# uThermometer.net
KiCad netlist of a schematic drawn in Altium Designer
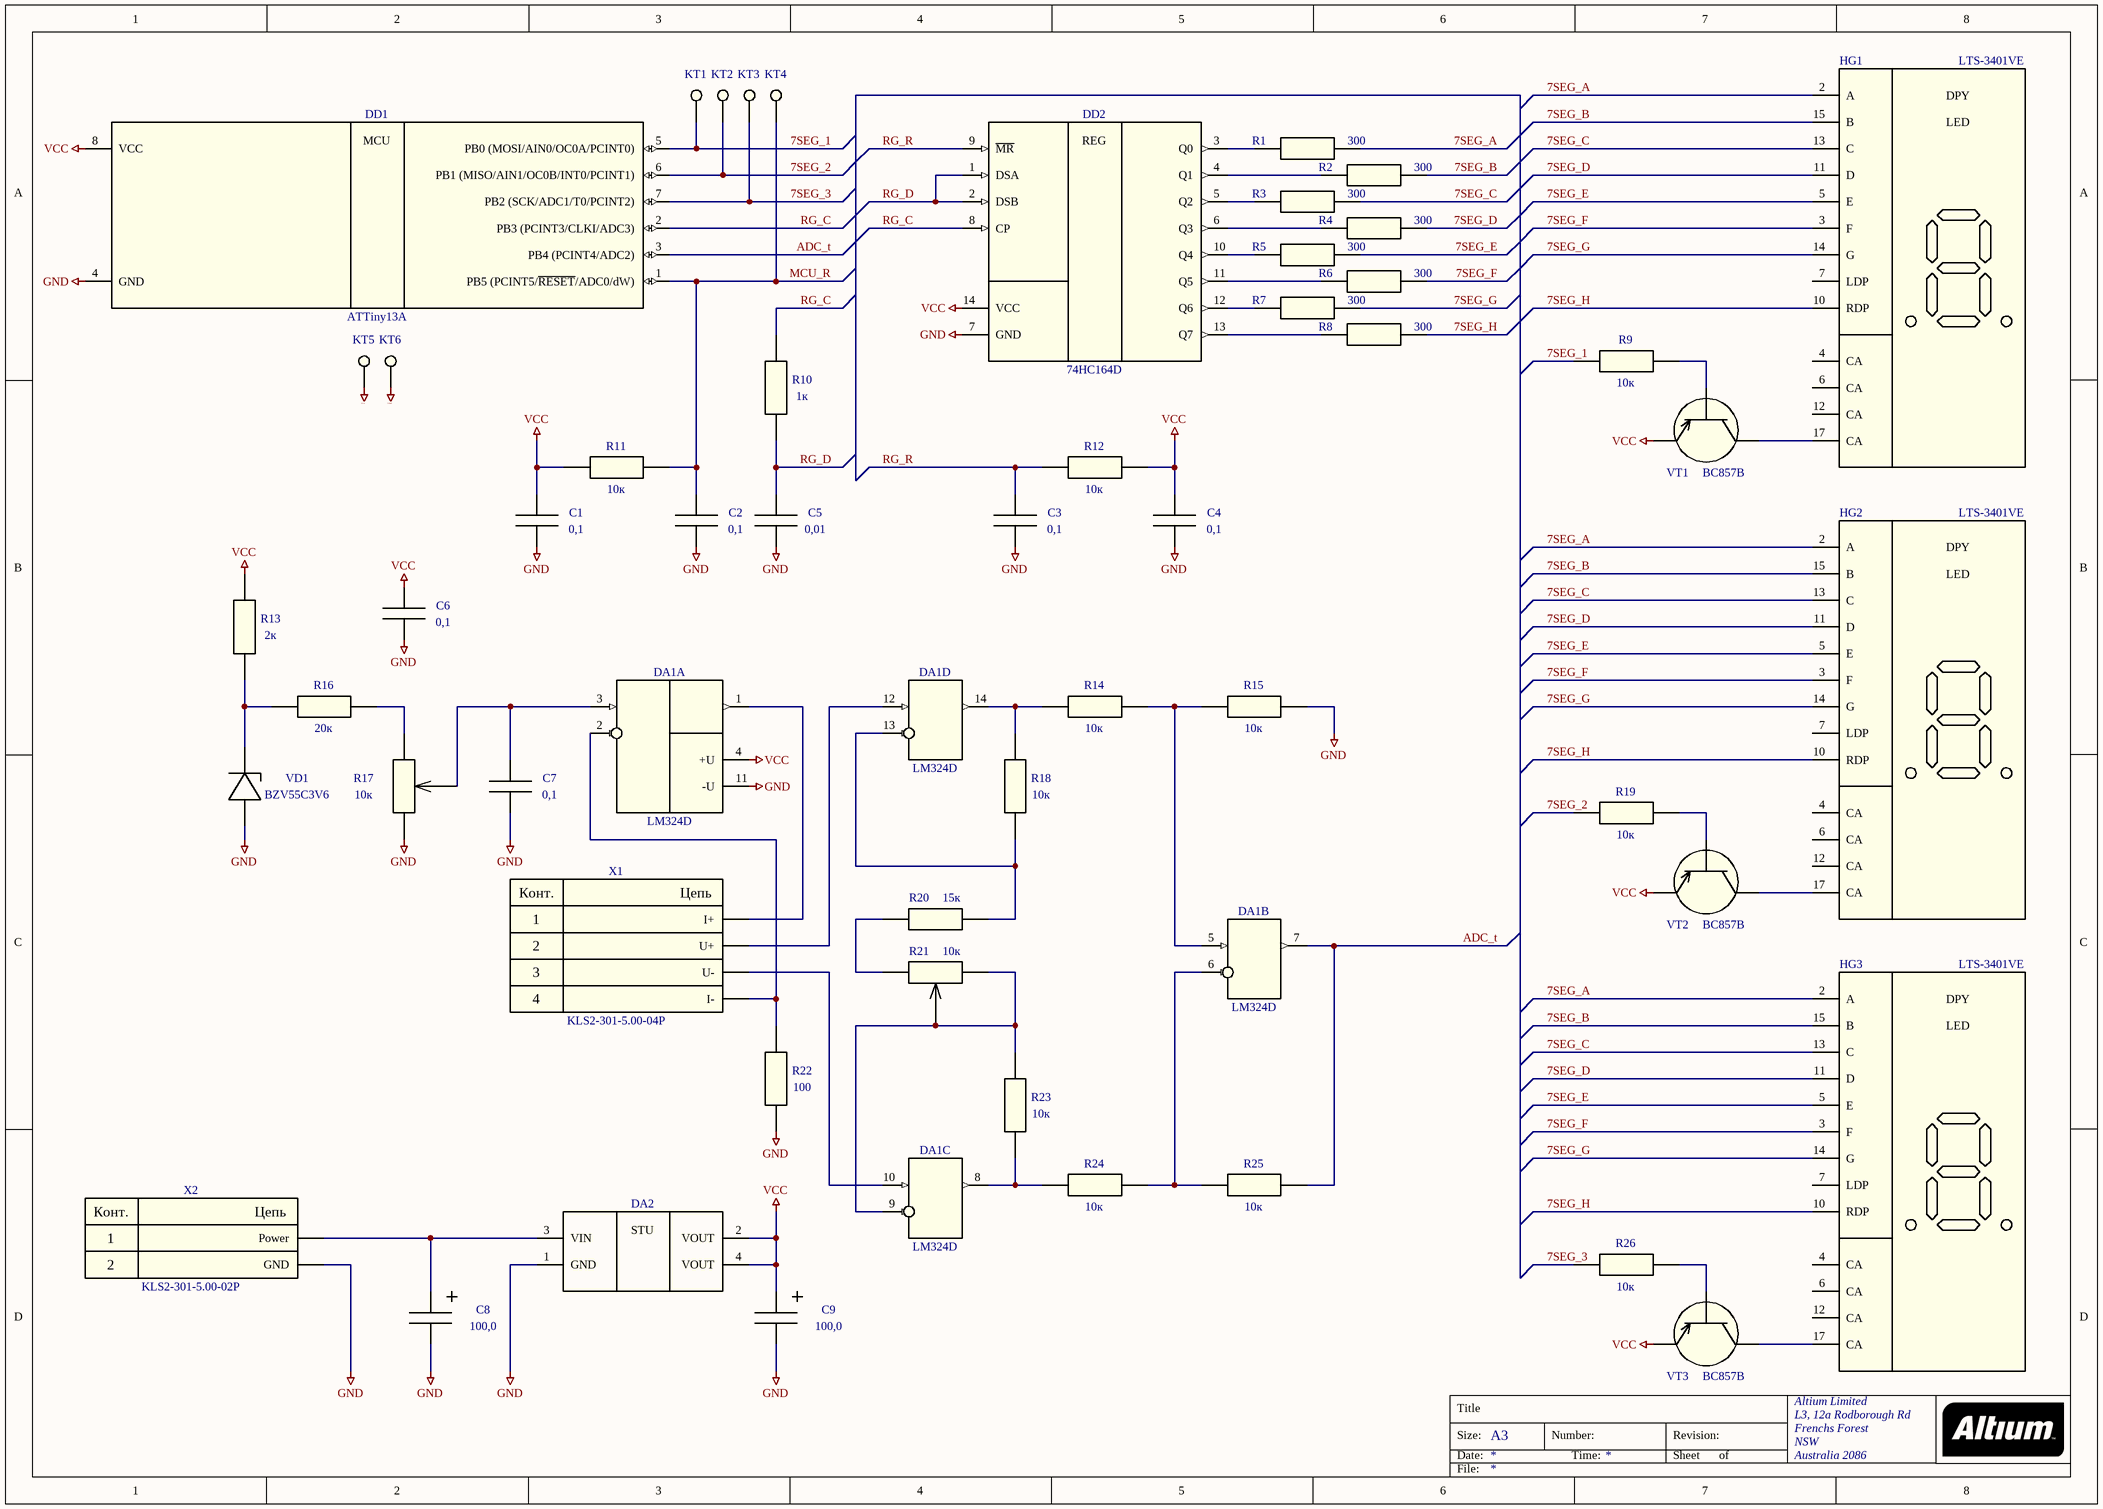
[diagram p0: uThermometer.SchDoc]

(export (version "E")
  (design (tool "Eeschema 10.0.6"))
  (components
    (comp (ref "C1")
      (value "0,1")
      (footprint "Capacitor SMD0805")
      (libsource (lib "IVV_Passive") (part "Capacitor C0805_100n"))
    )
    (comp (ref "C2")
      (value "0,1")
      (footprint "Capacitor SMD0805")
      (libsource (lib "IVV_Passive") (part "Capacitor C0805_100n"))
    )
    (comp (ref "C3")
      (value "0,1")
      (footprint "Capacitor SMD0805")
      (libsource (lib "IVV_Passive") (part "Capacitor C0805_100n"))
    )
    (comp (ref "C4")
      (value "0,1")
      (footprint "Capacitor SMD0805")
      (libsource (lib "IVV_Passive") (part "Capacitor C0805_100n"))
    )
    (comp (ref "C5")
      (value "0,01")
      (footprint "Capacitor SMD0805")
      (libsource (lib "IVV_Passive") (part "Capacitor C0805_10n"))
    )
    (comp (ref "C6")
      (value "0,1")
      (footprint "Capacitor SMD0805")
      (libsource (lib "IVV_Passive") (part "Capacitor C0805_100n"))
    )
    (comp (ref "C7")
      (value "0,1")
      (footprint "Capacitor SMD0805")
      (libsource (lib "IVV_Passive") (part "Capacitor C0805_100n"))
    )
    (comp (ref "C8")
      (value "100,0")
      (footprint "Capacitor R5V")
      (libsource (lib "IVV_Passive") (part "Capacitor R5V"))
    )
    (comp (ref "C9")
      (value "100,0")
      (footprint "Capacitor R5V")
      (libsource (lib "IVV_Passive") (part "Capacitor R5V"))
    )
    (comp (ref "DA1") (value "LM324D") (footprint "IC LM324D") (libsource (lib "IVV_IC") (part "IC LM324D")))
    (comp (ref "DA2")
      (value "LM1117I-5.0")
      (footprint "IC LM1117I-5.0")
      (libsource (lib "IVV_IC") (part "IC LM1117I-5.0"))
    )
    (comp (ref "DD1")
      (value "ATTiny13A")
      (footprint "IC ATTiny13A")
      (libsource (lib "IVV_IC") (part "IC ATTiny13A"))
    )
    (comp (ref "DD2")
      (value "74HC164D")
      (footprint "IC 74HC164D")
      (libsource (lib "IVV_IC") (part "IC 74HC164D"))
    )
    (comp (ref "HG1")
      (value "LTS-3401VE")
      (footprint "Indicator LTS3401VE")
      (libsource (lib "IVV_Lib") (part "Indicator LTS-3401VE"))
    )
    (comp (ref "HG2")
      (value "LTS-3401VE")
      (footprint "Indicator LTS3401VE")
      (libsource (lib "IVV_Lib") (part "Indicator LTS-3401VE"))
    )
    (comp (ref "HG3")
      (value "LTS-3401VE")
      (footprint "Indicator LTS3401VE")
      (libsource (lib "IVV_Lib") (part "Indicator LTS-3401VE"))
    )
    (comp (ref "KT1")
      (value "TestPoint 1")
      (footprint "TestPoint 1")
      (libsource (lib "IVV_Lib") (part "TestPoint 1"))
    )
    (comp (ref "KT2")
      (value "TestPoint 1")
      (footprint "TestPoint 1")
      (libsource (lib "IVV_Lib") (part "TestPoint 1"))
    )
    (comp (ref "KT3")
      (value "TestPoint 1")
      (footprint "TestPoint 1")
      (libsource (lib "IVV_Lib") (part "TestPoint 1"))
    )
    (comp (ref "KT4")
      (value "TestPoint 1")
      (footprint "TestPoint 1")
      (libsource (lib "IVV_Lib") (part "TestPoint 1"))
    )
    (comp (ref "KT5")
      (value "TestPoint 1")
      (footprint "TestPoint 1")
      (libsource (lib "IVV_Lib") (part "TestPoint 1"))
    )
    (comp (ref "KT6")
      (value "TestPoint 1")
      (footprint "TestPoint 1")
      (libsource (lib "IVV_Lib") (part "TestPoint 1"))
    )
    (comp (ref "R1")
      (value "300")
      (footprint "Resistor SMD0805")
      (libsource (lib "IVV_Passive") (part "Resistor R0805_300_5%"))
    )
    (comp (ref "R2")
      (value "300")
      (footprint "Resistor SMD0805")
      (libsource (lib "IVV_Passive") (part "Resistor R0805_300_5%"))
    )
    (comp (ref "R3")
      (value "300")
      (footprint "Resistor SMD0805")
      (libsource (lib "IVV_Passive") (part "Resistor R0805_300_5%"))
    )
    (comp (ref "R4")
      (value "300")
      (footprint "Resistor SMD0805")
      (libsource (lib "IVV_Passive") (part "Resistor R0805_300_5%"))
    )
    (comp (ref "R5")
      (value "300")
      (footprint "Resistor SMD0805")
      (libsource (lib "IVV_Passive") (part "Resistor R0805_300_5%"))
    )
    (comp (ref "R6")
      (value "300")
      (footprint "Resistor SMD0805")
      (libsource (lib "IVV_Passive") (part "Resistor R0805_300_5%"))
    )
    (comp (ref "R7")
      (value "300")
      (footprint "Resistor SMD0805")
      (libsource (lib "IVV_Passive") (part "Resistor R0805_300_5%"))
    )
    (comp (ref "R8")
      (value "300")
      (footprint "Resistor SMD0805")
      (libsource (lib "IVV_Passive") (part "Resistor R0805_300_5%"))
    )
    (comp (ref "R9")
      (value "10к")
      (footprint "Resistor SMD0805")
      (libsource (lib "IVV_Passive") (part "Resistor R0805_10k_5%"))
    )
    (comp (ref "R10")
      (value "1к")
      (footprint "Resistor SMD0805")
      (libsource (lib "IVV_Passive") (part "Resistor R0805_1k_5%"))
    )
    (comp (ref "R11")
      (value "10к")
      (footprint "Resistor SMD0805")
      (libsource (lib "IVV_Passive") (part "Resistor R0805_10k_5%"))
    )
    (comp (ref "R12")
      (value "10к")
      (footprint "Resistor SMD0805")
      (libsource (lib "") (part "Resistor R0805_10k_5%_1"))
    )
    (comp (ref "R13")
      (value "2к")
      (footprint "Resistor SMD0805")
      (libsource (lib "IVV_Passive") (part "Resistor R0805_2k_5%"))
    )
    (comp (ref "R14")
      (value "10к")
      (footprint "Resistor SMD0805")
      (libsource (lib "IVV_Passive") (part "Resistor R0805_10k_5%"))
    )
    (comp (ref "R15")
      (value "10к")
      (footprint "Resistor SMD0805")
      (libsource (lib "IVV_Passive") (part "Resistor R0805_10k_5%"))
    )
    (comp (ref "R16")
      (value "20к")
      (footprint "Resistor SMD0805")
      (libsource (lib "IVV_Passive") (part "Resistor R0805_20k_5%"))
    )
    (comp (ref "R17")
      (value "10к")
      (footprint "Resistor 3296W")
      (libsource (lib "") (part "Resistor 3296W _10k_1%_1"))
    )
    (comp (ref "R18")
      (value "10к")
      (footprint "Resistor SMD0805")
      (libsource (lib "") (part "Resistor R0805_10k_5%_2"))
    )
    (comp (ref "R19")
      (value "10к")
      (footprint "Resistor SMD0805")
      (libsource (lib "IVV_Passive") (part "Resistor R0805_10k_5%"))
    )
    (comp (ref "R20")
      (value "15к")
      (footprint "Resistor SMD0805")
      (libsource (lib "IVV_Passive") (part "Resistor R0805_15k_5%"))
    )
    (comp (ref "R21")
      (value "10к")
      (footprint "Resistor 3296W")
      (libsource (lib "IVV_Passive") (part "Resistor 3296W _10k_1%"))
    )
    (comp (ref "R22")
      (value "100")
      (footprint "Resistor SMD0805")
      (libsource (lib "IVV_Passive") (part "Resistor R0805_100_5%"))
    )
    (comp (ref "R23")
      (value "10к")
      (footprint "Resistor SMD0805")
      (libsource (lib "") (part "Resistor R0805_10k_5%_2"))
    )
    (comp (ref "R24")
      (value "10к")
      (footprint "Resistor SMD0805")
      (libsource (lib "IVV_Passive") (part "Resistor R0805_10k_5%"))
    )
    (comp (ref "R25")
      (value "10к")
      (footprint "Resistor SMD0805")
      (libsource (lib "IVV_Passive") (part "Resistor R0805_10k_5%"))
    )
    (comp (ref "R26")
      (value "10к")
      (footprint "Resistor SMD0805")
      (libsource (lib "IVV_Passive") (part "Resistor R0805_10k_5%"))
    )
    (comp (ref "VD1")
      (value "BZV55C3V6")
      (footprint "Zener BZV55C")
      (libsource (lib "IVV_Lib") (part "Zener BZV55C3V6"))
    )
    (comp (ref "VT1")
      (value "BC857B")
      (footprint "Transistor SOT23")
      (libsource (lib "IVV_Lib") (part "Transistor BC857B"))
    )
    (comp (ref "VT2")
      (value "BC857B")
      (footprint "Transistor SOT23")
      (libsource (lib "IVV_Lib") (part "Transistor BC857B"))
    )
    (comp (ref "VT3")
      (value "BC857B")
      (footprint "Transistor SOT23")
      (libsource (lib "IVV_Lib") (part "Transistor BC857B"))
    )
    (comp (ref "X1")
      (value "KLS2-301-5.00-04P")
      (footprint "Terminal KLS2-301-5.00-04P")
      (libsource (lib "IVV_Connectors") (part "Terminal KLS2-301-5.00-04P"))
    )
    (comp (ref "X2")
      (value "KLS2-301-5.00-02P")
      (footprint "Terminal KLS2-301-5.00-02P")
      (libsource (lib "IVV_Connectors") (part "Terminal KLS2-301-5.00-02P"))
    )
  )
  (nets
    (net (code "1") (name "/7SEG_1") (class "Default")
      (node (ref "DD1") (pin "5") (pinfunction "PB0_(MOSI/AIN0/OC0A/PCINT0)_5") (pintype "bidirectional"))
      (node (ref "KT1") (pin "1") (pinfunction "1_1") (pintype "passive"))
      (node (ref "R9") (pin "1") (pinfunction "1_1") (pintype "passive"))
    )
    (net (code "2") (name "/7SEG_2") (class "Default")
      (node (ref "DD1") (pin "6") (pinfunction "PB1_(MISO/AIN1/OC0B/INT0/PCINT1)_6") (pintype "bidirectional"))
      (node (ref "KT2") (pin "1") (pinfunction "1_1") (pintype "passive"))
      (node (ref "R19") (pin "1") (pinfunction "1_1") (pintype "passive"))
    )
    (net (code "3") (name "/7SEG_3") (class "Default")
      (node (ref "DD1") (pin "7") (pinfunction "PB2_(SCK/ADC1/T0/PCINT2)_7") (pintype "bidirectional"))
      (node (ref "KT3") (pin "1") (pinfunction "1_1") (pintype "passive"))
      (node (ref "R26") (pin "1") (pinfunction "1_1") (pintype "passive"))
    )
    (net (code "4") (name "/7SEG_A") (class "Default")
      (node (ref "HG1") (pin "2") (pinfunction "A_2") (pintype "passive"))
      (node (ref "HG2") (pin "2") (pinfunction "A_2") (pintype "passive"))
      (node (ref "HG3") (pin "2") (pinfunction "A_2") (pintype "passive"))
      (node (ref "R1") (pin "1") (pinfunction "1_1") (pintype "passive"))
    )
    (net (code "5") (name "/7SEG_B") (class "Default")
      (node (ref "HG1") (pin "15") (pinfunction "B_15") (pintype "passive"))
      (node (ref "HG2") (pin "15") (pinfunction "B_15") (pintype "passive"))
      (node (ref "HG3") (pin "15") (pinfunction "B_15") (pintype "passive"))
      (node (ref "R2") (pin "1") (pinfunction "1_1") (pintype "passive"))
    )
    (net (code "6") (name "/7SEG_C") (class "Default")
      (node (ref "HG1") (pin "13") (pinfunction "C_13") (pintype "passive"))
      (node (ref "HG2") (pin "13") (pinfunction "C_13") (pintype "passive"))
      (node (ref "HG3") (pin "13") (pinfunction "C_13") (pintype "passive"))
      (node (ref "R3") (pin "1") (pinfunction "1_1") (pintype "passive"))
    )
    (net (code "7") (name "/7SEG_D") (class "Default")
      (node (ref "HG1") (pin "11") (pinfunction "D_11") (pintype "passive"))
      (node (ref "HG2") (pin "11") (pinfunction "D_11") (pintype "passive"))
      (node (ref "HG3") (pin "11") (pinfunction "D_11") (pintype "passive"))
      (node (ref "R4") (pin "1") (pinfunction "1_1") (pintype "passive"))
    )
    (net (code "8") (name "/7SEG_E") (class "Default")
      (node (ref "HG1") (pin "5") (pinfunction "E_5") (pintype "passive"))
      (node (ref "HG2") (pin "5") (pinfunction "E_5") (pintype "passive"))
      (node (ref "HG3") (pin "5") (pinfunction "E_5") (pintype "passive"))
      (node (ref "R5") (pin "1") (pinfunction "1_1") (pintype "passive"))
    )
    (net (code "9") (name "/7SEG_F") (class "Default")
      (node (ref "HG1") (pin "3") (pinfunction "F_3") (pintype "passive"))
      (node (ref "HG2") (pin "3") (pinfunction "F_3") (pintype "passive"))
      (node (ref "HG3") (pin "3") (pinfunction "F_3") (pintype "passive"))
      (node (ref "R6") (pin "1") (pinfunction "1_1") (pintype "passive"))
    )
    (net (code "10") (name "/7SEG_G") (class "Default")
      (node (ref "HG1") (pin "14") (pinfunction "G_14") (pintype "passive"))
      (node (ref "HG2") (pin "14") (pinfunction "G_14") (pintype "passive"))
      (node (ref "HG3") (pin "14") (pinfunction "G_14") (pintype "passive"))
      (node (ref "R7") (pin "1") (pinfunction "1_1") (pintype "passive"))
    )
    (net (code "11") (name "/7SEG_H") (class "Default")
      (node (ref "HG1") (pin "10") (pinfunction "RDP_10") (pintype "passive"))
      (node (ref "HG2") (pin "10") (pinfunction "RDP_10") (pintype "passive"))
      (node (ref "HG3") (pin "10") (pinfunction "RDP_10") (pintype "passive"))
      (node (ref "R8") (pin "1") (pinfunction "1_1") (pintype "passive"))
    )
    (net (code "12") (name "/ADC_t") (class "Default")
      (node (ref "DA1") (pin "7") (pinfunction "OUTB_7") (pintype "output"))
      (node (ref "DD1") (pin "3") (pinfunction "PB4_(PCINT4/ADC2)_3") (pintype "bidirectional"))
      (node (ref "R25") (pin "2") (pinfunction "2_2") (pintype "passive"))
    )
    (net (code "13") (name "/MCU_R") (class "Default")
      (node (ref "C2") (pin "2") (pinfunction "2_2") (pintype "passive"))
      (node (ref "DD1") (pin "1") (pinfunction "PB5_(PCINT5/~{RESET}/ADC0/dW)_1") (pintype "bidirectional"))
      (node (ref "KT4") (pin "1") (pinfunction "1_1") (pintype "passive"))
      (node (ref "R11") (pin "2") (pinfunction "2_2") (pintype "passive"))
    )
    (net (code "14") (name "/RG_C") (class "Default")
      (node (ref "DD1") (pin "2") (pinfunction "PB3_(PCINT3/CLKI/ADC3)_2") (pintype "bidirectional"))
      (node (ref "DD2") (pin "8") (pinfunction "CP_8") (pintype "input"))
      (node (ref "R10") (pin "1") (pinfunction "1_1") (pintype "passive"))
    )
    (net (code "15") (name "/RG_D") (class "Default")
      (node (ref "C5") (pin "2") (pinfunction "2_2") (pintype "passive"))
      (node (ref "DD2") (pin "1") (pinfunction "DSA_1") (pintype "input"))
      (node (ref "DD2") (pin "2") (pinfunction "DSB_2") (pintype "input"))
      (node (ref "R10") (pin "2") (pinfunction "2_2") (pintype "passive"))
    )
    (net (code "16") (name "/RG_R") (class "Default")
      (node (ref "C3") (pin "2") (pinfunction "2_2") (pintype "passive"))
      (node (ref "DD2") (pin "9") (pinfunction "~{MR}_9") (pintype "input"))
      (node (ref "R12") (pin "2") (pinfunction "2_2") (pintype "passive"))
    )
    (net (code "17") (name "GND") (class "Default")
      (node (ref "C1") (pin "1") (pinfunction "1_1") (pintype "passive"))
      (node (ref "C2") (pin "1") (pinfunction "1_1") (pintype "passive"))
      (node (ref "C3") (pin "1") (pinfunction "1_1") (pintype "passive"))
      (node (ref "C4") (pin "1") (pinfunction "1_1") (pintype "passive"))
      (node (ref "C5") (pin "1") (pinfunction "1_1") (pintype "passive"))
      (node (ref "C6") (pin "1") (pinfunction "1_1") (pintype "passive"))
      (node (ref "C7") (pin "1") (pinfunction "1_1") (pintype "passive"))
      (node (ref "C8") (pin "2") (pinfunction "2_2") (pintype "passive"))
      (node (ref "C9") (pin "2") (pinfunction "2_2") (pintype "passive"))
      (node (ref "DA1") (pin "11") (pinfunction "-U_11") (pintype "power_in"))
      (node (ref "DA2") (pin "1") (pinfunction "GND_1") (pintype "power_in"))
      (node (ref "DD1") (pin "4") (pinfunction "GND_4") (pintype "power_in"))
      (node (ref "DD2") (pin "7") (pinfunction "GND_7") (pintype "power_in"))
      (node (ref "KT6") (pin "1") (pinfunction "1_1") (pintype "passive"))
      (node (ref "R15") (pin "2") (pinfunction "2_2") (pintype "passive"))
      (node (ref "R17") (pin "1") (pinfunction "1_1") (pintype "passive"))
      (node (ref "R22") (pin "1") (pinfunction "1_1") (pintype "passive"))
      (node (ref "VD1") (pin "1") (pinfunction "A_1") (pintype "passive"))
      (node (ref "X2") (pin "2") (pinfunction "GND_2") (pintype "passive"))
    )
    (net (code "18") (name "Net-(C8-+)") (class "Default")
      (node (ref "C8") (pin "1") (pinfunction "+_1") (pintype "passive"))
      (node (ref "DA2") (pin "3") (pinfunction "VIN_3") (pintype "power_in"))
      (node (ref "X2") (pin "1") (pinfunction "Power_1") (pintype "passive"))
    )
    (net (code "19") (name "Net-(DA1A-+INA)") (class "Default")
      (node (ref "C7") (pin "2") (pinfunction "2_2") (pintype "passive"))
      (node (ref "DA1") (pin "3") (pinfunction "+INA_3") (pintype "input"))
      (node (ref "R17") (pin "2") (pinfunction "2_2") (pintype "passive"))
    )
    (net (code "20") (name "Net-(DA1A--INA)") (class "Default")
      (node (ref "DA1") (pin "2") (pinfunction "-INA_2") (pintype "input"))
      (node (ref "R22") (pin "2") (pinfunction "2_2") (pintype "passive"))
      (node (ref "X1") (pin "4") (pinfunction "I-_4") (pintype "power_in"))
    )
    (net (code "21") (name "Net-(DA1A-OUTA)") (class "Default")
      (node (ref "DA1") (pin "1") (pinfunction "OUTA_1") (pintype "output"))
      (node (ref "X1") (pin "1") (pinfunction "I+_1") (pintype "passive"))
    )
    (net (code "22") (name "Net-(DA1B-INB+)") (class "Default")
      (node (ref "DA1") (pin "5") (pinfunction "INB+_5") (pintype "input"))
      (node (ref "R14") (pin "2") (pinfunction "2_2") (pintype "passive"))
      (node (ref "R15") (pin "1") (pinfunction "1_1") (pintype "passive"))
    )
    (net (code "23") (name "Net-(DA1B-INB-)") (class "Default")
      (node (ref "DA1") (pin "6") (pinfunction "INB-_6") (pintype "input"))
      (node (ref "R24") (pin "2") (pinfunction "2_2") (pintype "passive"))
      (node (ref "R25") (pin "1") (pinfunction "1_1") (pintype "passive"))
    )
    (net (code "24") (name "Net-(DA1C-INC+)") (class "Default")
      (node (ref "DA1") (pin "10") (pinfunction "INC+_10") (pintype "input"))
      (node (ref "X1") (pin "3") (pinfunction "U-_3") (pintype "power_in"))
    )
    (net (code "25") (name "Net-(DA1C-INC-)") (class "Default")
      (node (ref "DA1") (pin "9") (pinfunction "INC-_9") (pintype "input"))
      (node (ref "R21") (pin "1") (pinfunction "1_1") (pintype "passive"))
      (node (ref "R21") (pin "2") (pinfunction "2_2") (pintype "passive"))
      (node (ref "R23") (pin "2") (pinfunction "2_2") (pintype "passive"))
    )
    (net (code "26") (name "Net-(DA1C-OUTC)") (class "Default")
      (node (ref "DA1") (pin "8") (pinfunction "OUTC_8") (pintype "output"))
      (node (ref "R23") (pin "1") (pinfunction "1_1") (pintype "passive"))
      (node (ref "R24") (pin "1") (pinfunction "1_1") (pintype "passive"))
    )
    (net (code "27") (name "Net-(DA1D-IND+)") (class "Default")
      (node (ref "DA1") (pin "12") (pinfunction "IND+_12") (pintype "input"))
      (node (ref "X1") (pin "2") (pinfunction "U+_2") (pintype "passive"))
    )
    (net (code "28") (name "Net-(DA1D-IND-)") (class "Default")
      (node (ref "DA1") (pin "13") (pinfunction "IND-_13") (pintype "input"))
      (node (ref "R18") (pin "1") (pinfunction "1_1") (pintype "passive"))
      (node (ref "R20") (pin "2") (pinfunction "2_2") (pintype "passive"))
    )
    (net (code "29") (name "Net-(DA1D-OUTD)") (class "Default")
      (node (ref "DA1") (pin "14") (pinfunction "OUTD_14") (pintype "output"))
      (node (ref "R14") (pin "1") (pinfunction "1_1") (pintype "passive"))
      (node (ref "R18") (pin "2") (pinfunction "2_2") (pintype "passive"))
    )
    (net (code "30") (name "Net-(DD2-Q0)") (class "Default")
      (node (ref "DD2") (pin "3") (pinfunction "Q0_3") (pintype "output"))
      (node (ref "R1") (pin "2") (pinfunction "2_2") (pintype "passive"))
    )
    (net (code "31") (name "Net-(DD2-Q1)") (class "Default")
      (node (ref "DD2") (pin "4") (pinfunction "Q1_4") (pintype "output"))
      (node (ref "R2") (pin "2") (pinfunction "2_2") (pintype "passive"))
    )
    (net (code "32") (name "Net-(DD2-Q2)") (class "Default")
      (node (ref "DD2") (pin "5") (pinfunction "Q2_5") (pintype "output"))
      (node (ref "R3") (pin "2") (pinfunction "2_2") (pintype "passive"))
    )
    (net (code "33") (name "Net-(DD2-Q3)") (class "Default")
      (node (ref "DD2") (pin "6") (pinfunction "Q3_6") (pintype "output"))
      (node (ref "R4") (pin "2") (pinfunction "2_2") (pintype "passive"))
    )
    (net (code "34") (name "Net-(DD2-Q4)") (class "Default")
      (node (ref "DD2") (pin "10") (pinfunction "Q4_10") (pintype "output"))
      (node (ref "R5") (pin "2") (pinfunction "2_2") (pintype "passive"))
    )
    (net (code "35") (name "Net-(DD2-Q5)") (class "Default")
      (node (ref "DD2") (pin "11") (pinfunction "Q5_11") (pintype "output"))
      (node (ref "R6") (pin "2") (pinfunction "2_2") (pintype "passive"))
    )
    (net (code "36") (name "Net-(DD2-Q6)") (class "Default")
      (node (ref "DD2") (pin "12") (pinfunction "Q6_12") (pintype "output"))
      (node (ref "R7") (pin "2") (pinfunction "2_2") (pintype "passive"))
    )
    (net (code "37") (name "Net-(DD2-Q7)") (class "Default")
      (node (ref "DD2") (pin "13") (pinfunction "Q7_13") (pintype "output"))
      (node (ref "R8") (pin "2") (pinfunction "2_2") (pintype "passive"))
    )
    (net (code "38") (name "Net-(R16-Pad2)") (class "Default")
      (node (ref "R16") (pin "2") (pinfunction "2_2") (pintype "passive"))
      (node (ref "R17") (pin "3") (pinfunction "3_3") (pintype "passive"))
    )
    (net (code "39") (name "Net-(R20-Pad1)") (class "Default")
      (node (ref "R20") (pin "1") (pinfunction "1_1") (pintype "passive"))
      (node (ref "R21") (pin "3") (pinfunction "3_3") (pintype "passive"))
    )
    (net (code "40") (name "Net-(VD1-C)") (class "Default")
      (node (ref "R13") (pin "1") (pinfunction "1_1") (pintype "passive"))
      (node (ref "R16") (pin "1") (pinfunction "1_1") (pintype "passive"))
      (node (ref "VD1") (pin "2") (pinfunction "C_2") (pintype "passive"))
    )
    (net (code "41") (name "Net-(VT1-B)") (class "Default")
      (node (ref "R9") (pin "2") (pinfunction "2_2") (pintype "passive"))
      (node (ref "VT1") (pin "1") (pinfunction "B_1") (pintype "passive"))
    )
    (net (code "42") (name "Net-(VT1-C)") (class "Default")
      (node (ref "HG1") (pin "17") (pinfunction "CA_17") (pintype "passive"))
      (node (ref "VT1") (pin "3") (pinfunction "C_3") (pintype "passive"))
    )
    (net (code "43") (name "Net-(VT2-B)") (class "Default")
      (node (ref "R19") (pin "2") (pinfunction "2_2") (pintype "passive"))
      (node (ref "VT2") (pin "1") (pinfunction "B_1") (pintype "passive"))
    )
    (net (code "44") (name "Net-(VT2-C)") (class "Default")
      (node (ref "HG2") (pin "17") (pinfunction "CA_17") (pintype "passive"))
      (node (ref "VT2") (pin "3") (pinfunction "C_3") (pintype "passive"))
    )
    (net (code "45") (name "Net-(VT3-B)") (class "Default")
      (node (ref "R26") (pin "2") (pinfunction "2_2") (pintype "passive"))
      (node (ref "VT3") (pin "1") (pinfunction "B_1") (pintype "passive"))
    )
    (net (code "46") (name "Net-(VT3-C)") (class "Default")
      (node (ref "HG3") (pin "17") (pinfunction "CA_17") (pintype "passive"))
      (node (ref "VT3") (pin "3") (pinfunction "C_3") (pintype "passive"))
    )
    (net (code "47") (name "VCC") (class "Default")
      (node (ref "C1") (pin "2") (pinfunction "2_2") (pintype "passive"))
      (node (ref "C4") (pin "2") (pinfunction "2_2") (pintype "passive"))
      (node (ref "C6") (pin "2") (pinfunction "2_2") (pintype "passive"))
      (node (ref "C9") (pin "1") (pinfunction "+_1") (pintype "passive"))
      (node (ref "DA1") (pin "4") (pinfunction "+U_4") (pintype "power_in"))
      (node (ref "DA2") (pin "2") (pinfunction "VOUT_2") (pintype "power_in"))
      (node (ref "DA2") (pin "4") (pinfunction "VOUT_4") (pintype "power_in"))
      (node (ref "DD1") (pin "8") (pinfunction "VCC_8") (pintype "power_in"))
      (node (ref "DD2") (pin "14") (pinfunction "VCC_14") (pintype "power_in"))
      (node (ref "KT5") (pin "1") (pinfunction "1_1") (pintype "passive"))
      (node (ref "R11") (pin "1") (pinfunction "1_1") (pintype "passive"))
      (node (ref "R12") (pin "1") (pinfunction "1_1") (pintype "passive"))
      (node (ref "R13") (pin "2") (pinfunction "2_2") (pintype "passive"))
      (node (ref "VT1") (pin "2") (pinfunction "E_2") (pintype "passive"))
      (node (ref "VT2") (pin "2") (pinfunction "E_2") (pintype "passive"))
      (node (ref "VT3") (pin "2") (pinfunction "E_2") (pintype "passive"))
    )
    (net (code "48") (name "unconnected-(HG1-CA-Pad4)") (class "Default")
      (node (ref "HG1") (pin "4") (pinfunction "CA_4") (pintype "passive"))
    )
    (net (code "49") (name "unconnected-(HG1-CA-Pad6)") (class "Default")
      (node (ref "HG1") (pin "6") (pinfunction "CA_6") (pintype "passive"))
    )
    (net (code "50") (name "unconnected-(HG1-CA-Pad12)") (class "Default")
      (node (ref "HG1") (pin "12") (pinfunction "CA_12") (pintype "passive"))
    )
    (net (code "51") (name "unconnected-(HG1-LDP-Pad7)") (class "Default")
      (node (ref "HG1") (pin "7") (pinfunction "LDP_7") (pintype "passive"))
    )
    (net (code "52") (name "unconnected-(HG2-CA-Pad4)") (class "Default")
      (node (ref "HG2") (pin "4") (pinfunction "CA_4") (pintype "passive"))
    )
    (net (code "53") (name "unconnected-(HG2-CA-Pad6)") (class "Default")
      (node (ref "HG2") (pin "6") (pinfunction "CA_6") (pintype "passive"))
    )
    (net (code "54") (name "unconnected-(HG2-CA-Pad12)") (class "Default")
      (node (ref "HG2") (pin "12") (pinfunction "CA_12") (pintype "passive"))
    )
    (net (code "55") (name "unconnected-(HG2-LDP-Pad7)") (class "Default")
      (node (ref "HG2") (pin "7") (pinfunction "LDP_7") (pintype "passive"))
    )
    (net (code "56") (name "unconnected-(HG3-CA-Pad4)") (class "Default")
      (node (ref "HG3") (pin "4") (pinfunction "CA_4") (pintype "passive"))
    )
    (net (code "57") (name "unconnected-(HG3-CA-Pad6)") (class "Default")
      (node (ref "HG3") (pin "6") (pinfunction "CA_6") (pintype "passive"))
    )
    (net (code "58") (name "unconnected-(HG3-CA-Pad12)") (class "Default")
      (node (ref "HG3") (pin "12") (pinfunction "CA_12") (pintype "passive"))
    )
    (net (code "59") (name "unconnected-(HG3-LDP-Pad7)") (class "Default")
      (node (ref "HG3") (pin "7") (pinfunction "LDP_7") (pintype "passive"))
    )
  )
)
